# PCB_Telemetria_2020.net
KiCad netlist of a schematic drawn in EAGLE
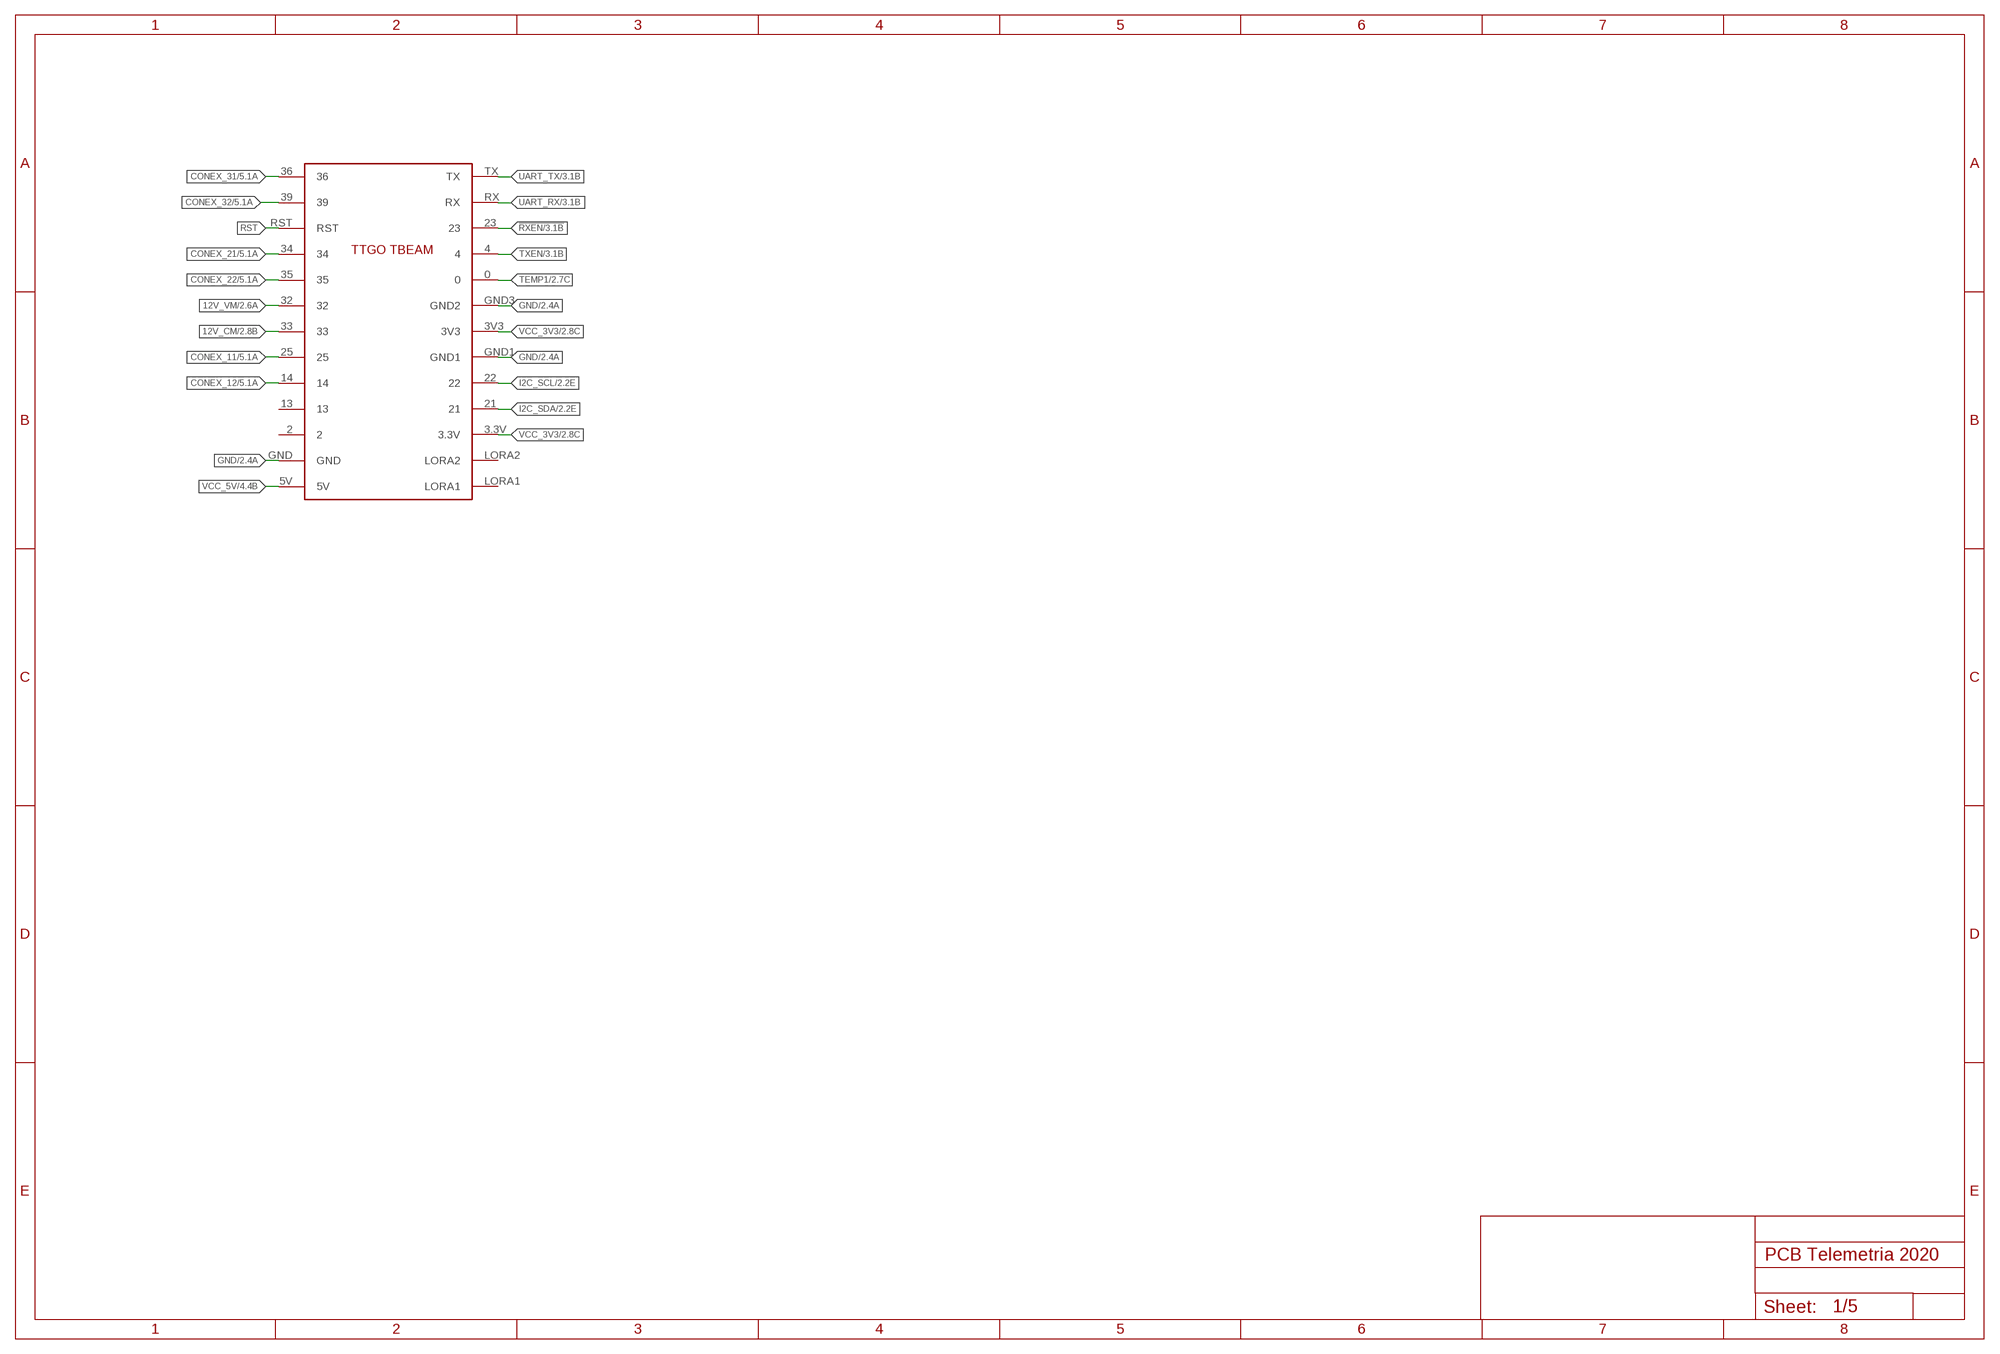
[diagram p0: schematic, sheet 1]
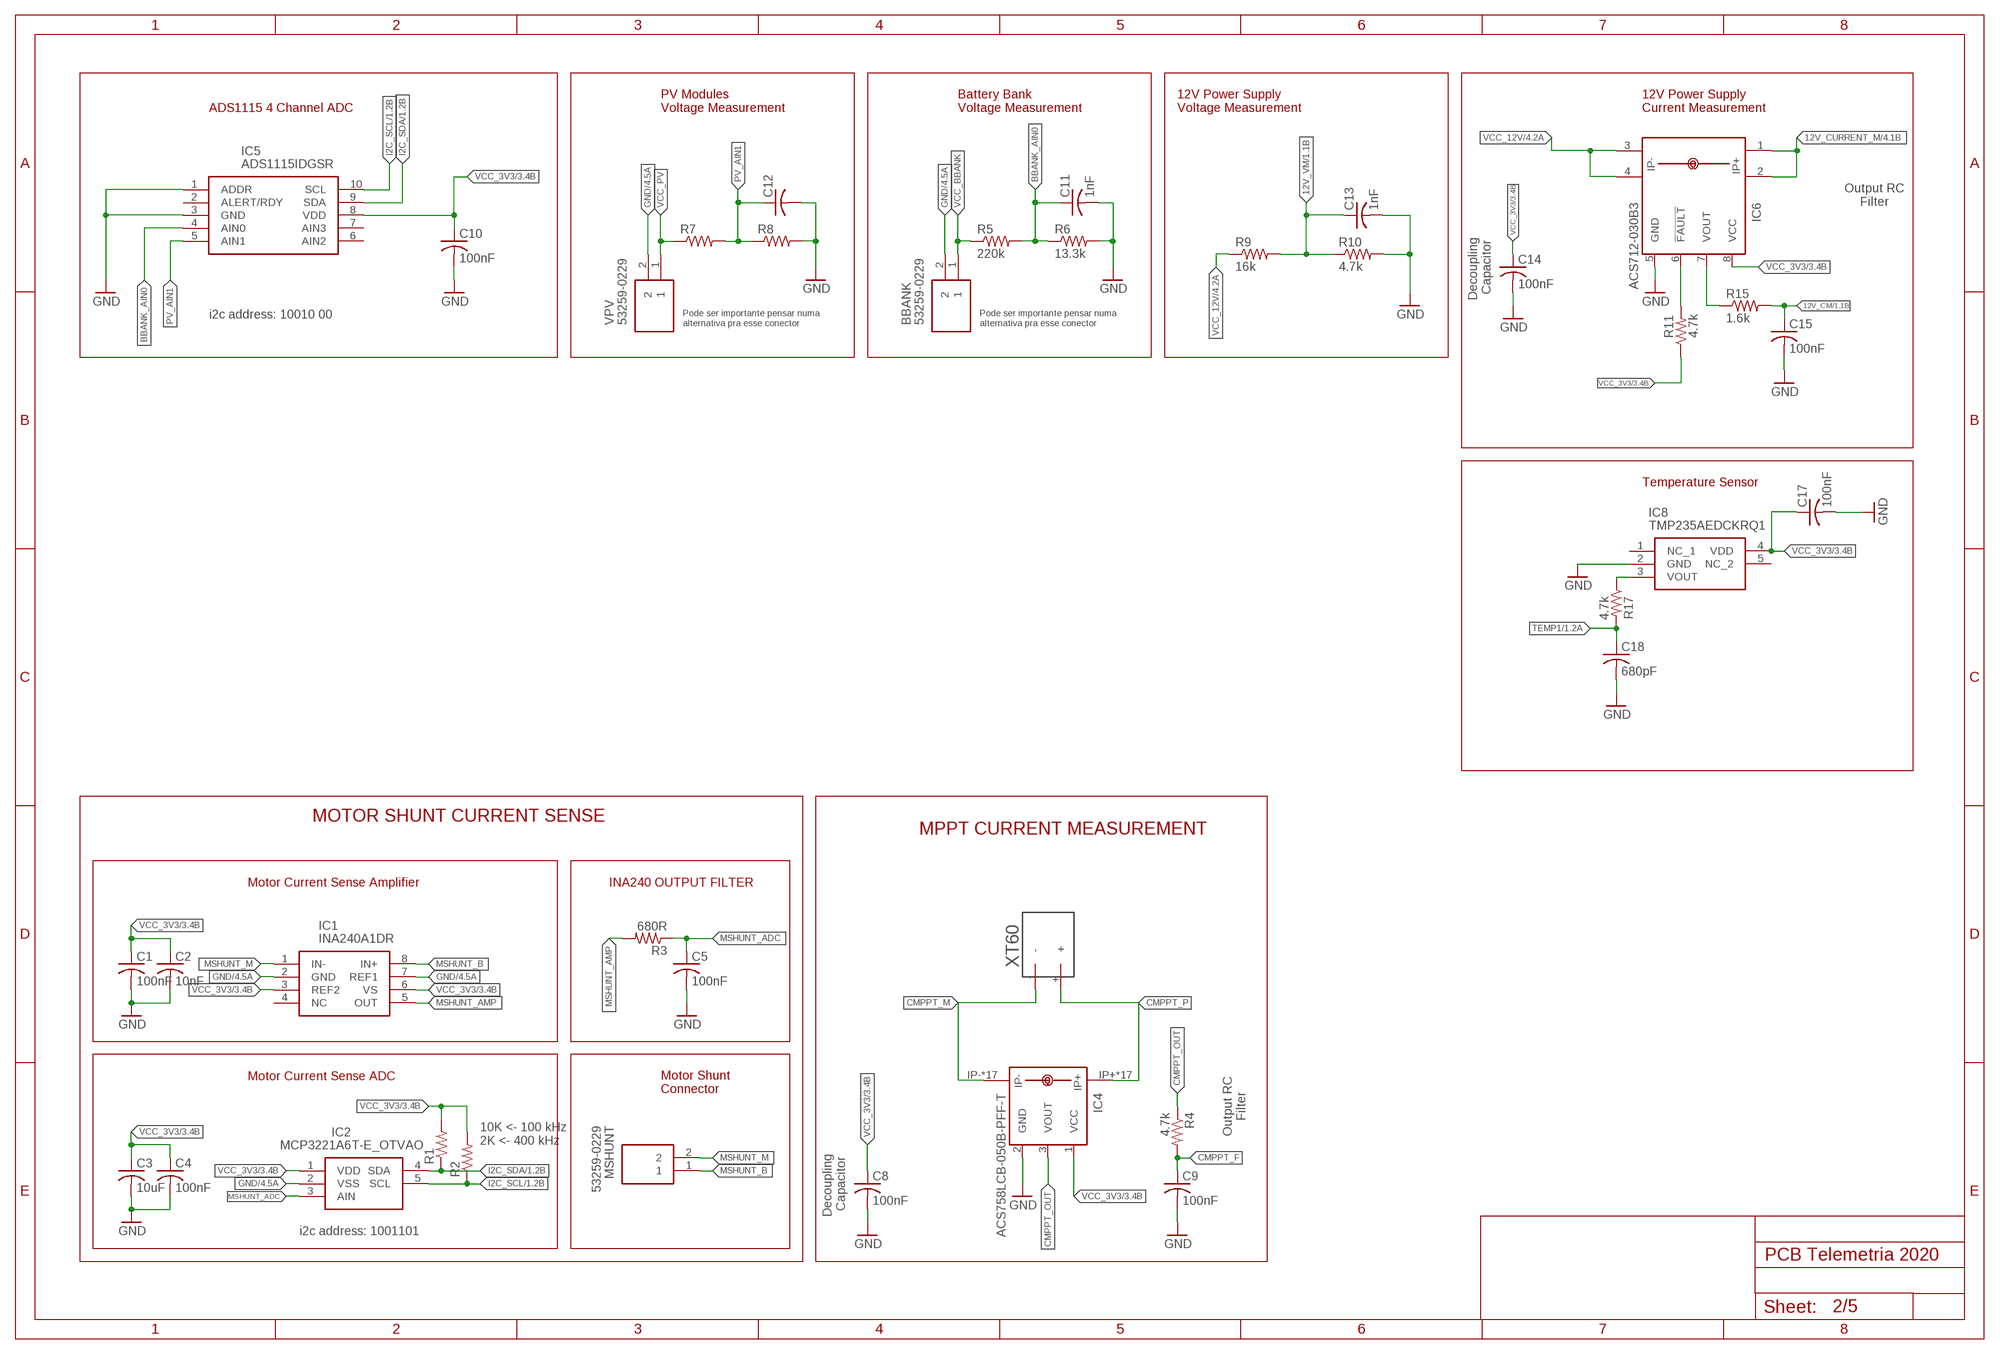
[diagram p1: schematic, sheet 2]
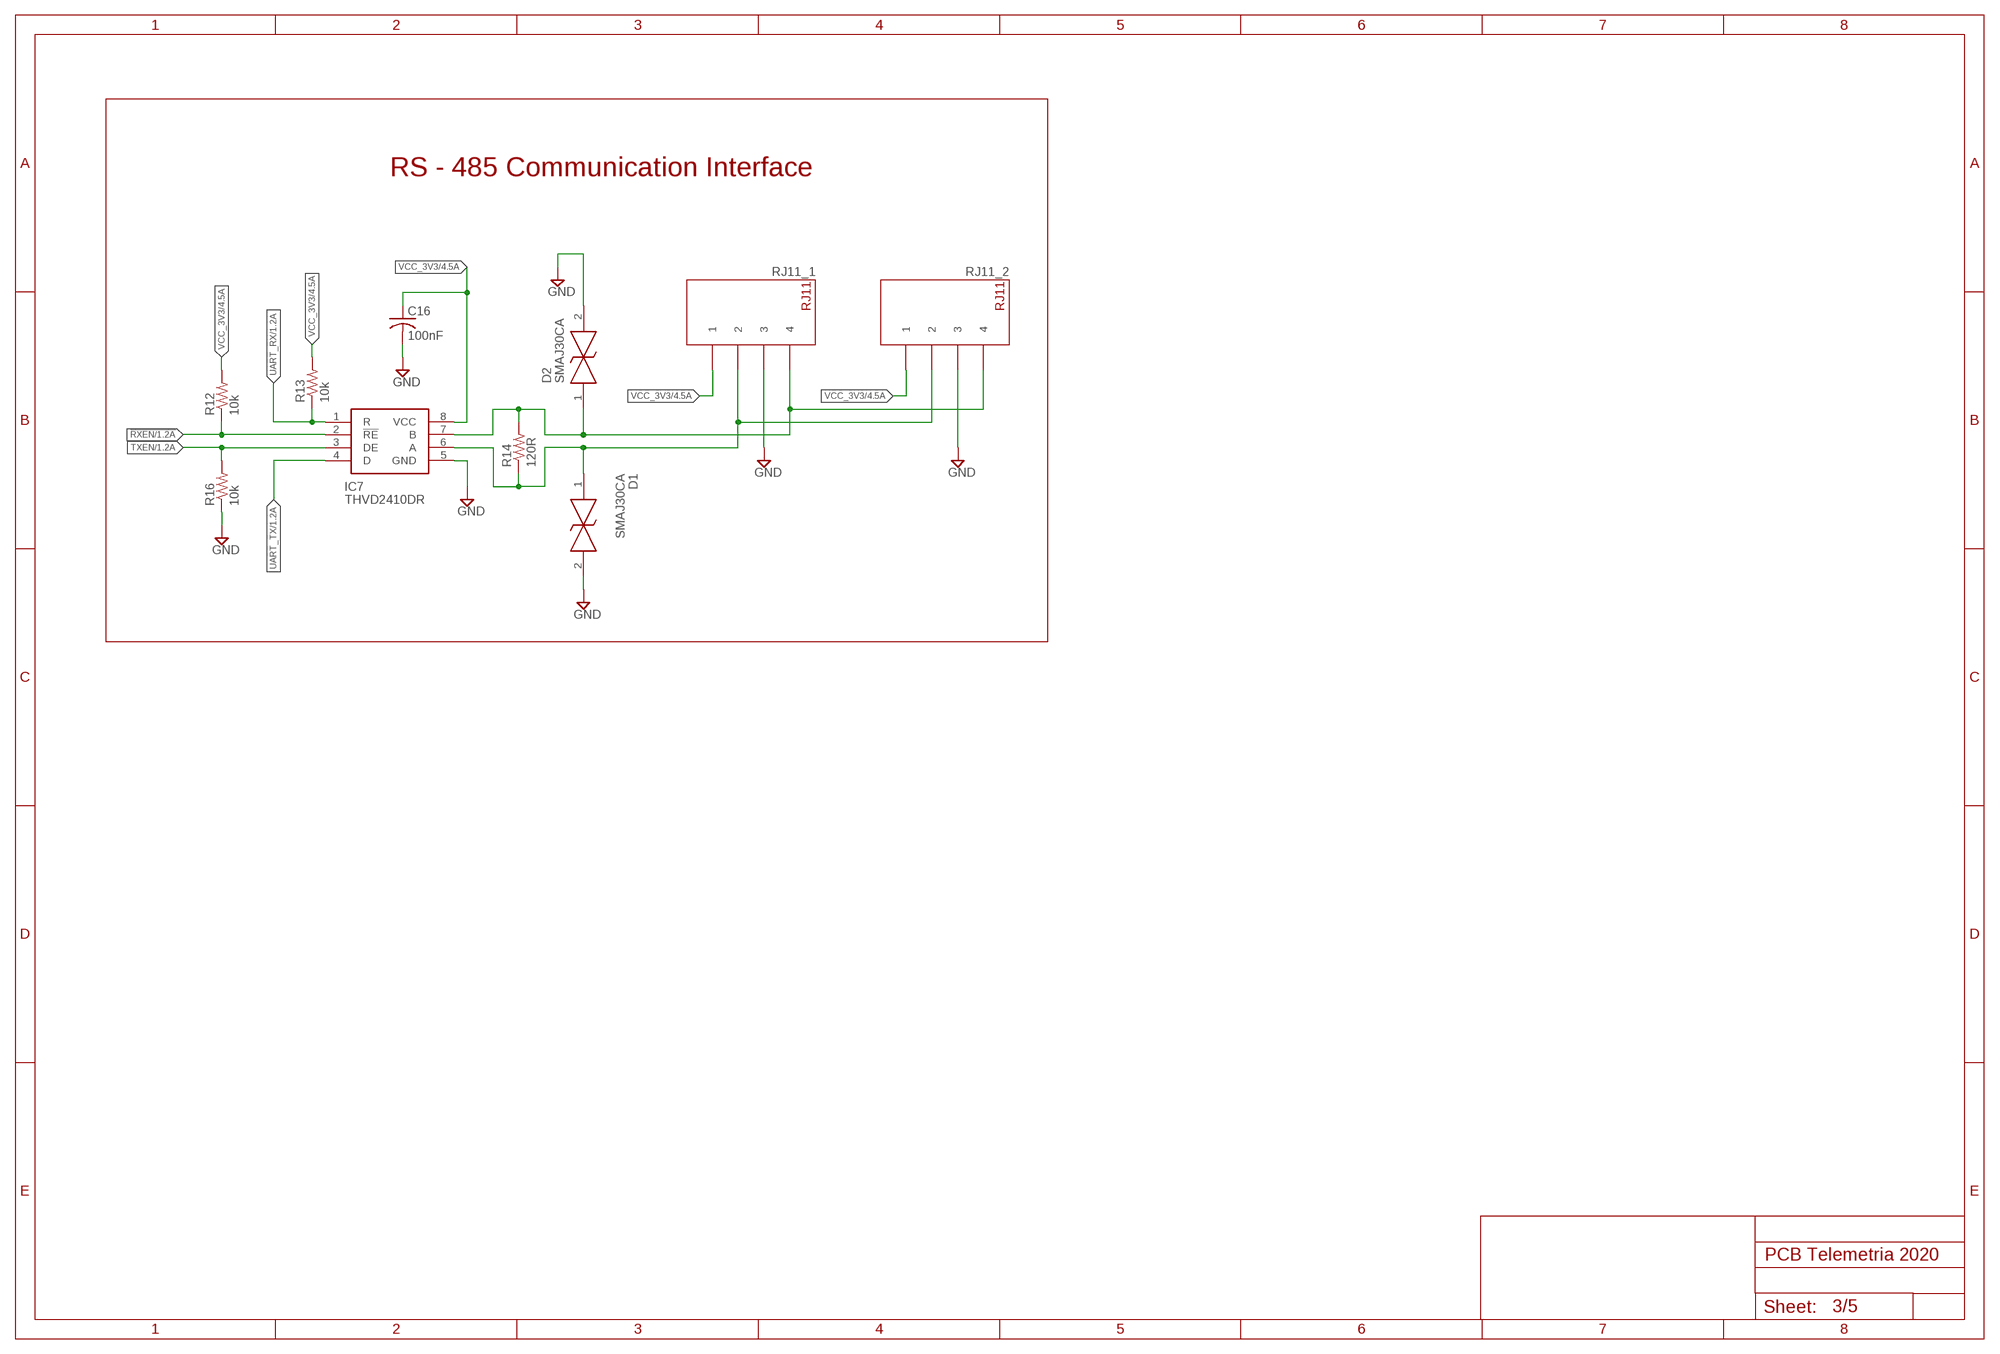
[diagram p2: schematic, sheet 3]
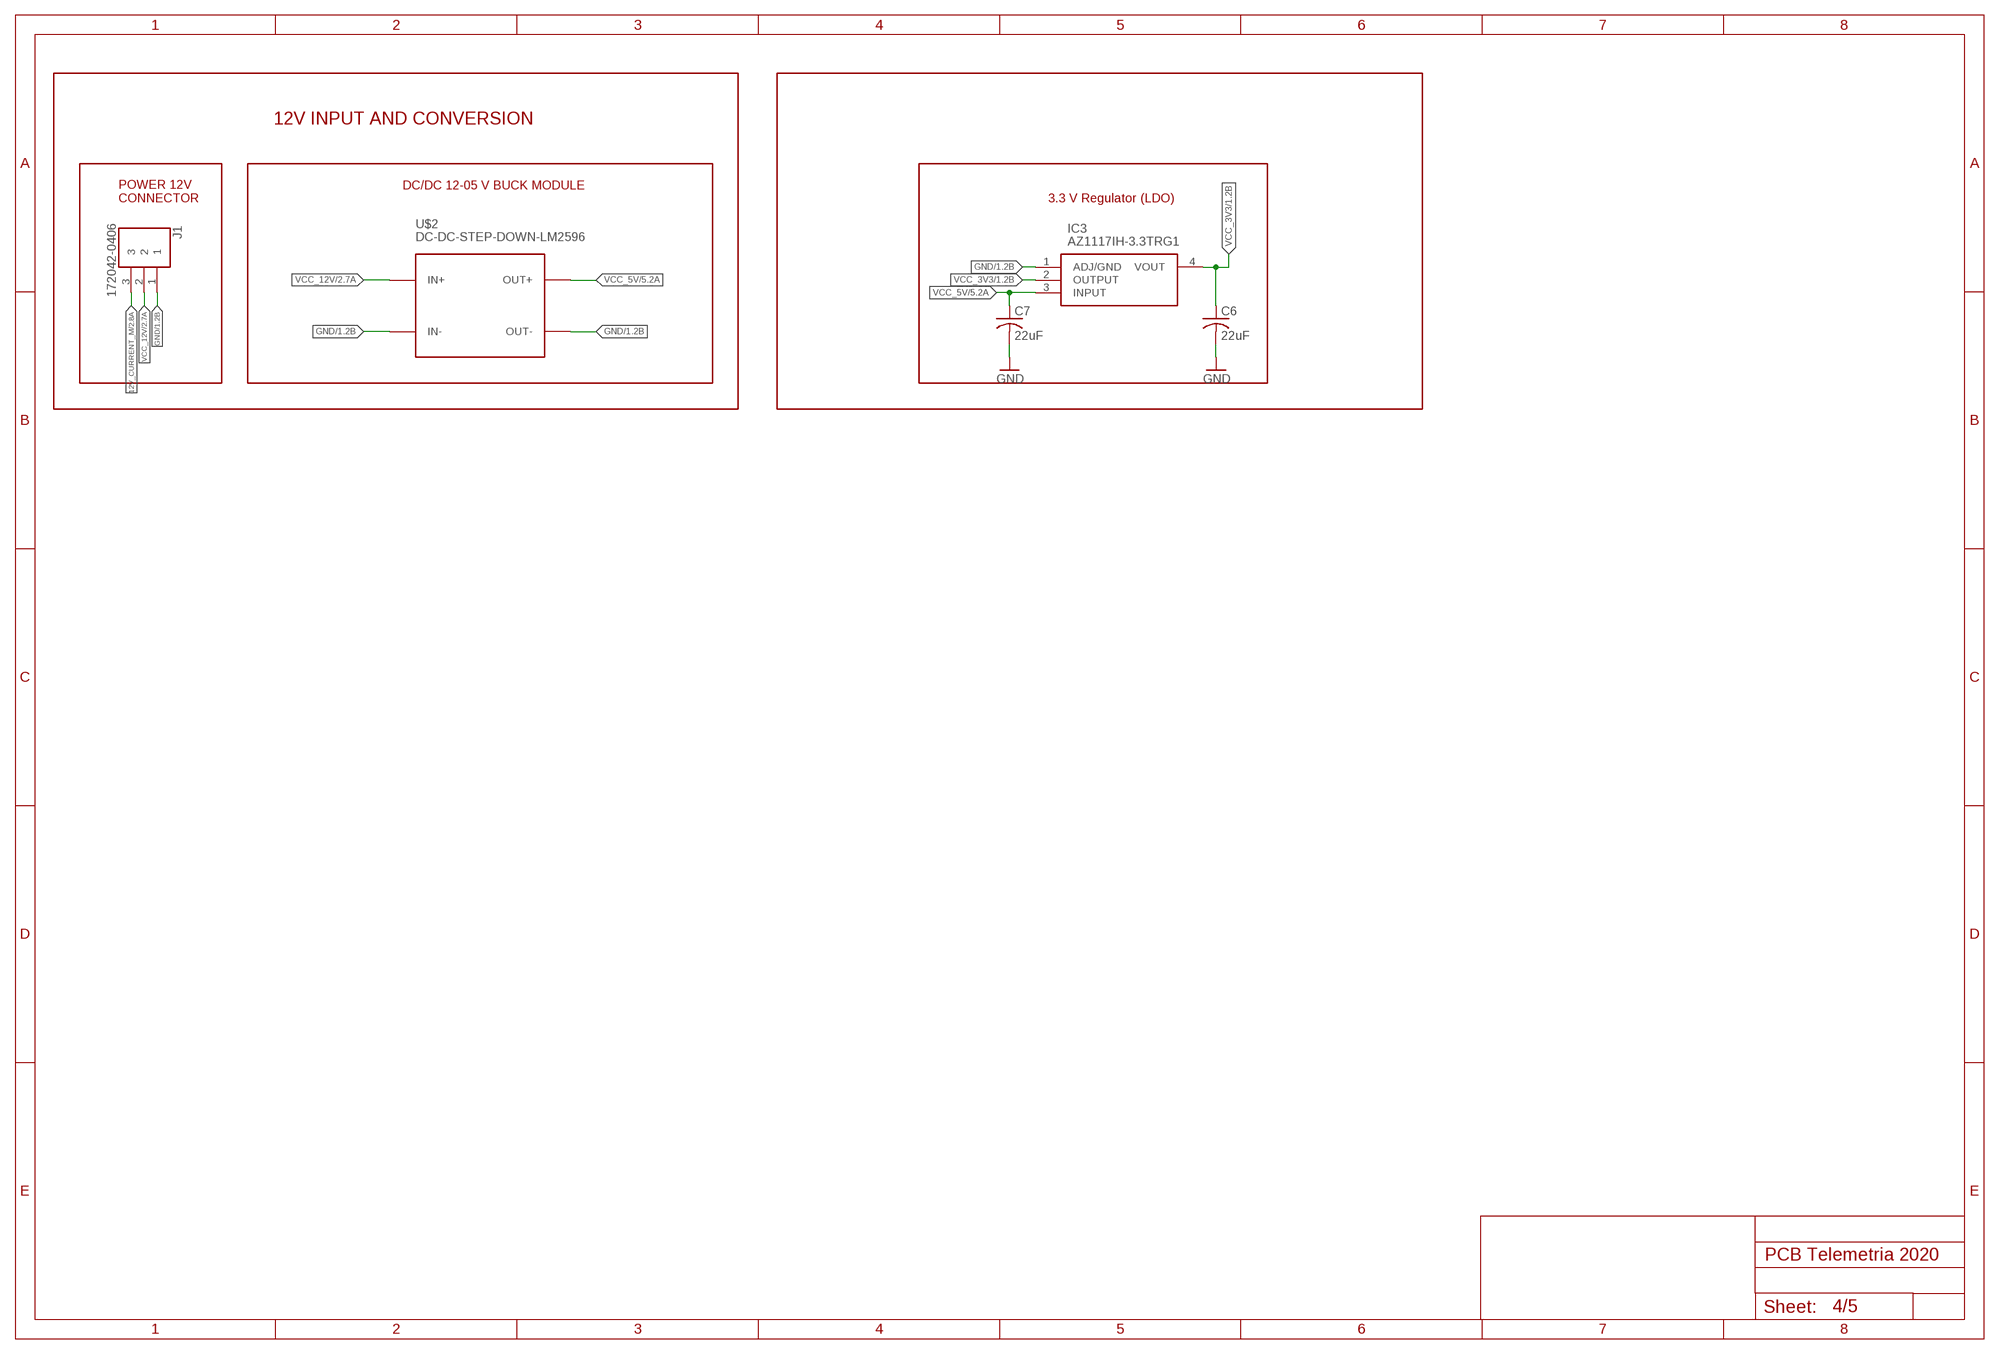
[diagram p3: schematic, sheet 4]
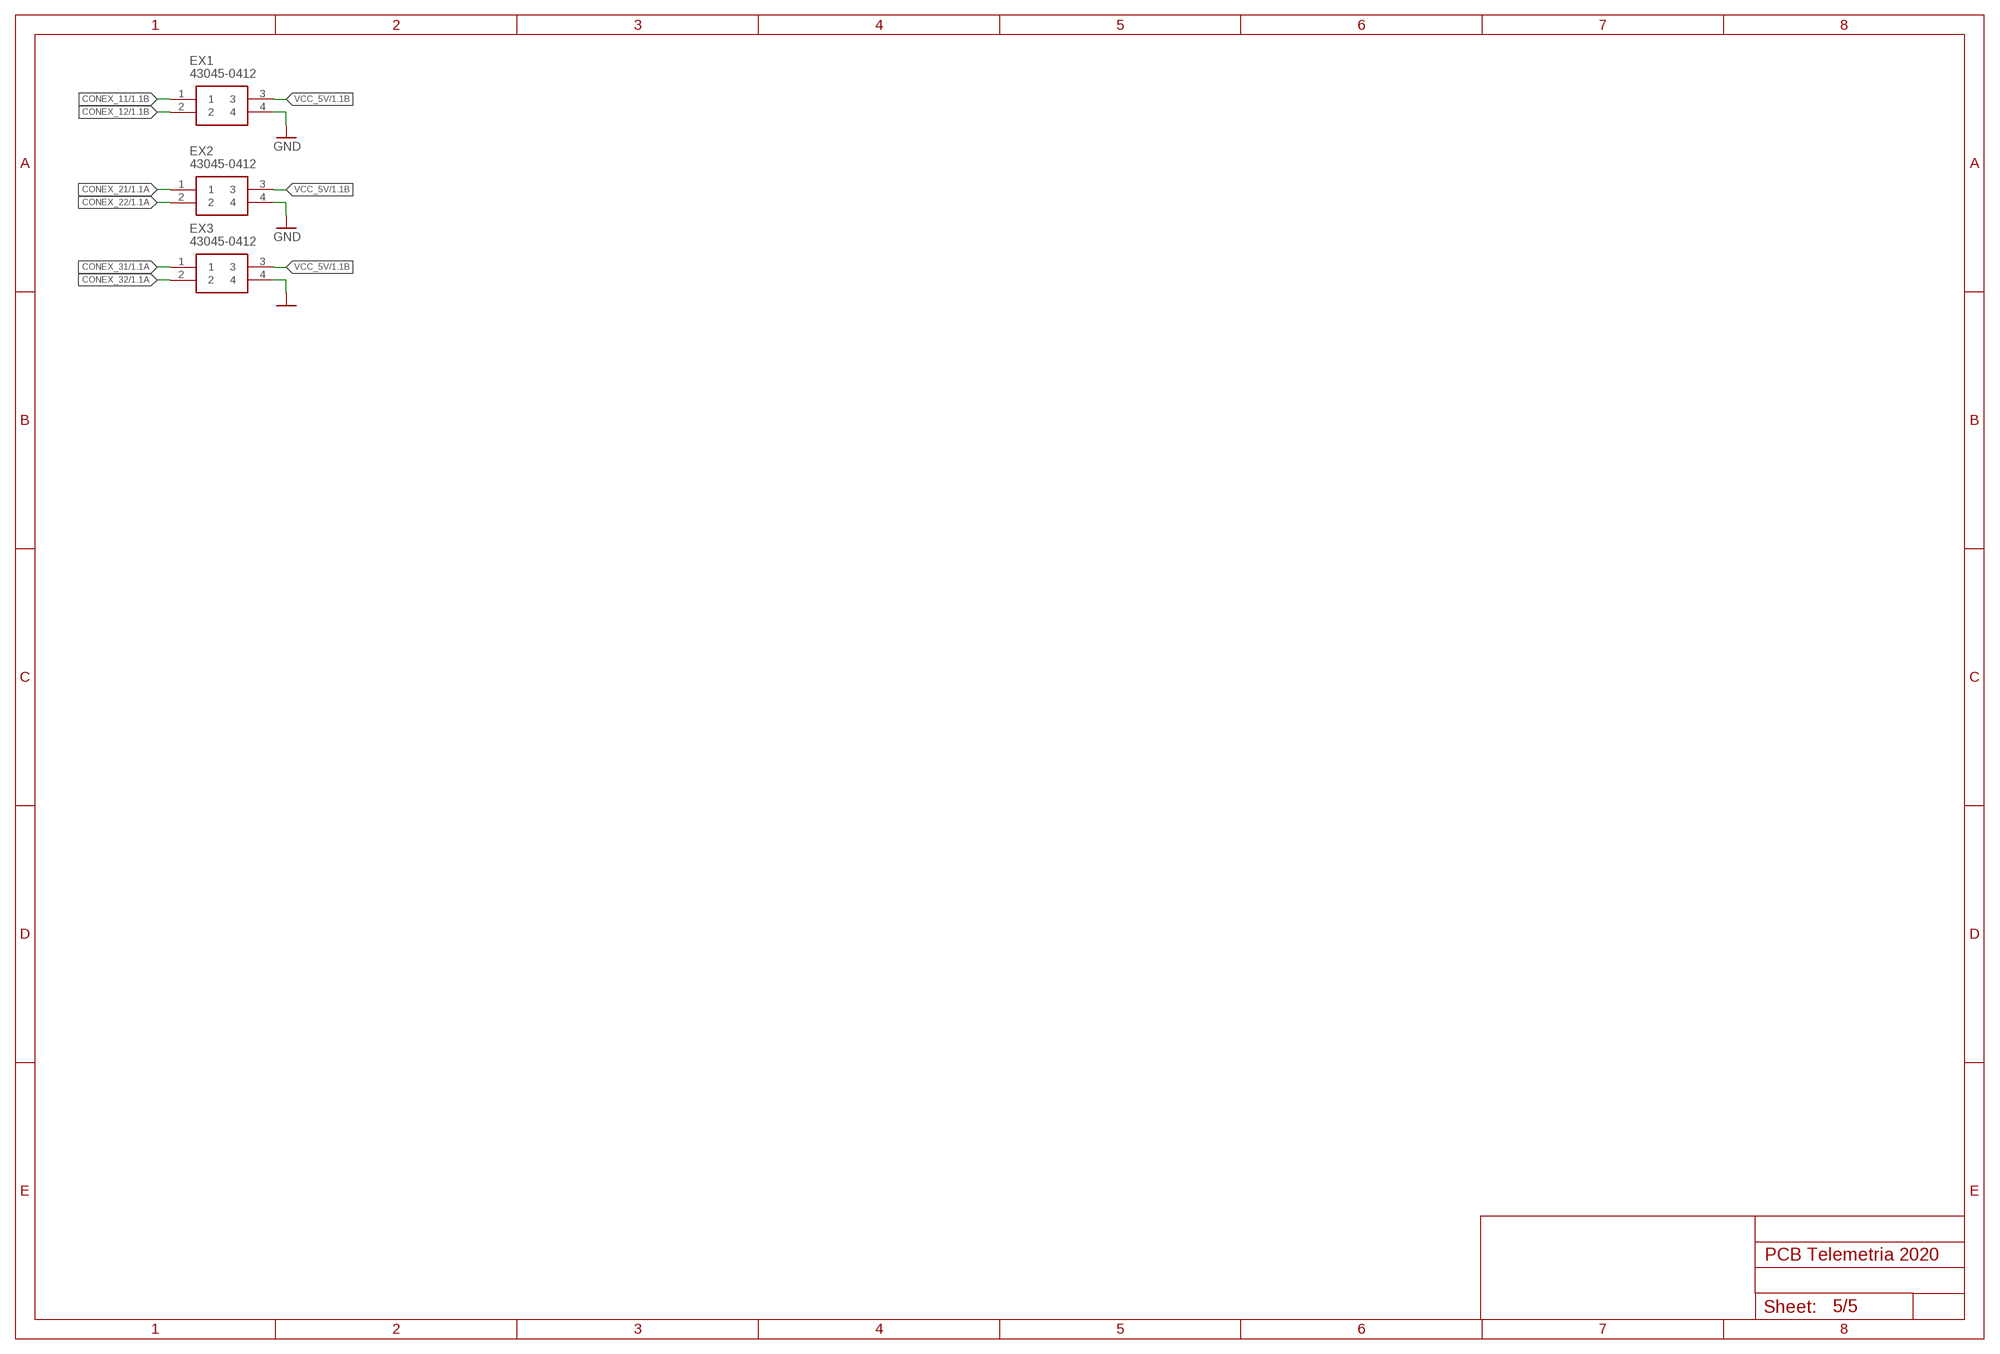
[diagram p4: schematic, sheet 5]

(export (version "E")
  (design (tool "Eeschema 10.0.6"))
  (components
    (comp (ref "C16")
      (value "100nF")
      (footprint "eagle-import:C0805")
      (libsource (lib "eagle-import") (part "C-USC0805"))
    )
    (comp (ref "D1")
      (value "SMAJ30CA")
      (footprint "eagle-import:DIONM5026X229N")
      (fields (field (name "MOUSER_PART_NUMBER") "576-SMAJ30CA"))
      (libsource (lib "eagle-import") (part "SMAJ30CA"))
    )
    (comp (ref "D2")
      (value "SMAJ30CA")
      (footprint "eagle-import:DIONM5026X229N")
      (fields (field (name "MOUSER_PART_NUMBER") "576-SMAJ30CA"))
      (libsource (lib "eagle-import") (part "SMAJ30CA"))
    )
    (comp (ref "IC7")
      (value "THVD2410DR")
      (footprint "eagle-import:SOIC127P600X175-8N")
      (fields (field (name "MOUSER_PART_NUMBER") "595-THVD2410DR"))
      (libsource (lib "eagle-import") (part "THVD2410DR"))
    )
    (comp (ref "R12")
      (value "10k")
      (footprint "eagle-import:M0805")
      (libsource (lib "eagle-import") (part "R-US_M0805"))
    )
    (comp (ref "R13")
      (value "10k")
      (footprint "eagle-import:M0805")
      (libsource (lib "eagle-import") (part "R-US_M0805"))
    )
    (comp (ref "R14")
      (value "120R")
      (footprint "eagle-import:M0805")
      (libsource (lib "eagle-import") (part "R-US_M0805"))
    )
    (comp (ref "R16")
      (value "10k")
      (footprint "eagle-import:M0805")
      (libsource (lib "eagle-import") (part "R-US_M0805"))
    )
    (comp (ref "RJ11_1")
      (value "TFC44")
      (footprint "eagle-import:TFC44")
      (libsource (lib "eagle-import") (part "TFC44"))
    )
    (comp (ref "RJ11_2")
      (value "TFC44")
      (footprint "eagle-import:TFC44")
      (libsource (lib "eagle-import") (part "TFC44"))
    )
    (comp (ref "EX1")
      (value "43045-0412")
      (footprint "eagle-import:43045-0412")
      (fields (field (name "MOUSER_PART_NUMBER") "538-43045-0412"))
      (libsource (lib "eagle-import") (part "43045-0412"))
    )
    (comp (ref "EX2")
      (value "43045-0412")
      (footprint "eagle-import:43045-0412")
      (fields (field (name "MOUSER_PART_NUMBER") "538-43045-0412"))
      (libsource (lib "eagle-import") (part "43045-0412"))
    )
    (comp (ref "EX3")
      (value "43045-0412")
      (footprint "eagle-import:43045-0412")
      (fields (field (name "MOUSER_PART_NUMBER") "538-43045-0412"))
      (libsource (lib "eagle-import") (part "43045-0412"))
    )
    (comp (ref "U$1")
      (value "TTGOBEAM")
      (footprint "eagle-import:TTGOBEAM")
      (libsource (lib "eagle-import") (part "TTGOBEAM"))
    )
    (comp (ref "BBANK")
      (value "53259-0229")
      (footprint "eagle-import:0532590229")
      (fields (field (name "MOUSER_PART_NUMBER") "538-53259-0229"))
      (libsource (lib "eagle-import") (part "53259-0229"))
    )
    (comp (ref "C1")
      (value "100nF")
      (footprint "eagle-import:C0805")
      (libsource (lib "eagle-import") (part "C-USC0805"))
    )
    (comp (ref "C2")
      (value "10nF")
      (footprint "eagle-import:C0805")
      (libsource (lib "eagle-import") (part "C-USC0805"))
    )
    (comp (ref "C3")
      (value "10uF")
      (footprint "eagle-import:C0805")
      (libsource (lib "eagle-import") (part "C-USC0805"))
    )
    (comp (ref "C4")
      (value "100nF")
      (footprint "eagle-import:C0805")
      (libsource (lib "eagle-import") (part "C-USC0805"))
    )
    (comp (ref "C5")
      (value "100nF")
      (footprint "eagle-import:C0805")
      (libsource (lib "eagle-import") (part "C-USC0805"))
    )
    (comp (ref "C8")
      (value "100nF")
      (footprint "eagle-import:C0805")
      (libsource (lib "eagle-import") (part "C-USC0805"))
    )
    (comp (ref "C9")
      (value "100nF")
      (footprint "eagle-import:C0805")
      (libsource (lib "eagle-import") (part "C-USC0805"))
    )
    (comp (ref "C10")
      (value "100nF")
      (footprint "eagle-import:C0805")
      (libsource (lib "eagle-import") (part "C-USC0805"))
    )
    (comp (ref "C11")
      (value "1nF")
      (footprint "eagle-import:C0805")
      (libsource (lib "eagle-import") (part "C-USC0805"))
    )
    (comp (ref "C12")
      (value "C-USC0805")
      (footprint "eagle-import:C0805")
      (libsource (lib "eagle-import") (part "C-USC0805"))
    )
    (comp (ref "C13")
      (value "1nF")
      (footprint "eagle-import:C0805")
      (libsource (lib "eagle-import") (part "C-USC0805"))
    )
    (comp (ref "C14")
      (value "100nF")
      (footprint "eagle-import:C0805")
      (libsource (lib "eagle-import") (part "C-USC0805"))
    )
    (comp (ref "C15")
      (value "100nF")
      (footprint "eagle-import:C0805")
      (libsource (lib "eagle-import") (part "C-USC0805"))
    )
    (comp (ref "C17")
      (value "100nF")
      (footprint "eagle-import:C0805")
      (libsource (lib "eagle-import") (part "C-USC0805"))
    )
    (comp (ref "C18")
      (value "680pF")
      (footprint "eagle-import:C0805")
      (libsource (lib "eagle-import") (part "C-USC0805"))
    )
    (comp (ref "IC1")
      (value "INA240A1DR")
      (footprint "eagle-import:SOIC127P600X175-8N")
      (fields (field (name "MOUSER_PART_NUMBER") "595-INA240A1DR"))
      (libsource (lib "eagle-import") (part "INA240A1DR"))
    )
    (comp (ref "IC2")
      (value "MCP3221A6T-E_OTVAO")
      (footprint "eagle-import:SOT95P280X145-5N")
      (fields
        (field (name "MANUFACTURER_PART_NUMBER") "MCP3221A6T-E/OTVAO")
        (field (name "MOUSER_PART_NUMBER") "579-MCP3221A6TEOTVAO")
      )
      (libsource (lib "eagle-import") (part "MCP3221A6T-E_OTVAO"))
    )
    (comp (ref "IC4")
      (value "ACS758LCB-050B-PFF-T")
      (footprint "eagle-import:CB-PFF")
      (libsource (lib "eagle-import") (part "ACS758LCB-050B-PFF-T"))
    )
    (comp (ref "IC5")
      (value "ADS1115IDGSR")
      (footprint "eagle-import:SOP50P490X110-10N")
      (fields (field (name "MOUSER_PART_NUMBER") "595-ADS1115IDGSR"))
      (libsource (lib "eagle-import") (part "ADS1115IDGSR"))
    )
    (comp (ref "IC6")
      (value "ACS712-030B3")
      (footprint "eagle-import:SOIC8")
      (libsource (lib "eagle-import") (part "ACS712-LC"))
    )
    (comp (ref "IC8")
      (value "TMP235AEDCKRQ1")
      (footprint "eagle-import:SOT65P210X110-5N")
      (fields (field (name "MOUSER_PART_NUMBER") "595-TMP235AEDCKRQ1"))
      (libsource (lib "eagle-import") (part "TMP235AEDCKRQ1"))
    )
    (comp (ref "MSHUNT")
      (value "53259-0229")
      (footprint "eagle-import:0532590229")
      (fields (field (name "MOUSER_PART_NUMBER") "538-53259-0229"))
      (libsource (lib "eagle-import") (part "53259-0229"))
    )
    (comp (ref "R1")
      (value "R-US_R0805")
      (footprint "eagle-import:R0805")
      (libsource (lib "eagle-import") (part "R-US_R0805"))
    )
    (comp (ref "R2")
      (value "R-US_R0805")
      (footprint "eagle-import:R0805")
      (libsource (lib "eagle-import") (part "R-US_R0805"))
    )
    (comp (ref "R3")
      (value "680R")
      (footprint "eagle-import:R0805")
      (libsource (lib "eagle-import") (part "R-US_R0805"))
    )
    (comp (ref "R4")
      (value "4.7k")
      (footprint "eagle-import:R0805")
      (libsource (lib "eagle-import") (part "R-US_R0805"))
    )
    (comp (ref "R5")
      (value "220k")
      (footprint "eagle-import:R0805")
      (libsource (lib "eagle-import") (part "R-US_R0805"))
    )
    (comp (ref "R6")
      (value "13.3k")
      (footprint "eagle-import:R0805")
      (libsource (lib "eagle-import") (part "R-US_R0805"))
    )
    (comp (ref "R7")
      (value "R-US_R0805")
      (footprint "eagle-import:R0805")
      (libsource (lib "eagle-import") (part "R-US_R0805"))
    )
    (comp (ref "R8")
      (value "R-US_R0805")
      (footprint "eagle-import:R0805")
      (libsource (lib "eagle-import") (part "R-US_R0805"))
    )
    (comp (ref "R9")
      (value "16k")
      (footprint "eagle-import:R0805")
      (libsource (lib "eagle-import") (part "R-US_R0805"))
    )
    (comp (ref "R10")
      (value "4.7k")
      (footprint "eagle-import:R0805")
      (libsource (lib "eagle-import") (part "R-US_R0805"))
    )
    (comp (ref "R11")
      (value "4.7k")
      (footprint "eagle-import:R0805")
      (libsource (lib "eagle-import") (part "R-US_R0805"))
    )
    (comp (ref "R15")
      (value "1.6k")
      (footprint "eagle-import:R0805")
      (libsource (lib "eagle-import") (part "R-US_R0805"))
    )
    (comp (ref "R17")
      (value "4.7k")
      (footprint "eagle-import:R0805")
      (libsource (lib "eagle-import") (part "R-US_R0805"))
    )
    (comp (ref "U$3")
      (value "XT60")
      (footprint "eagle-import:XT60")
      (libsource (lib "eagle-import") (part "XT60"))
    )
    (comp (ref "VPV")
      (value "53259-0229")
      (footprint "eagle-import:0532590229")
      (fields (field (name "MOUSER_PART_NUMBER") "538-53259-0229"))
      (libsource (lib "eagle-import") (part "53259-0229"))
    )
    (comp (ref "C6")
      (value "22uF")
      (footprint "eagle-import:C0805")
      (libsource (lib "eagle-import") (part "C-USC0805"))
    )
    (comp (ref "C7")
      (value "22uF")
      (footprint "eagle-import:C0805")
      (libsource (lib "eagle-import") (part "C-USC0805"))
    )
    (comp (ref "IC3")
      (value "AZ1117IH-3.3TRG1")
      (footprint "eagle-import:SOT230P700X170-4N")
      (fields (field (name "MOUSER_PART_NUMBER") "621-AZ1117IH-3.3TRG1"))
      (libsource (lib "eagle-import") (part "AZ1117IH-3.3TRG1"))
    )
    (comp (ref "J1")
      (value "172042-0406")
      (footprint "eagle-import:MOLEX_172042-0406")
      (fields (field (name "MF") "Molex") (field (name "MP") "172042-0302"))
      (libsource (lib "eagle-import") (part "172042-0406"))
    )
    (comp (ref "U$2")
      (value "DC-DC-STEP-DOWN-LM2596")
      (footprint "eagle-import:DC-DC-STEP-DOWN-LM2596")
      (libsource (lib "eagle-import") (part "DC-DC-STEP-DOWN-LM2596"))
    )
  )
  (nets
    (net (code "1") (name "12V_CM") (class "Default")
      (node (ref "C15") (pin "1") (pinfunction "1_1") (pintype "passive"))
      (node (ref "R15") (pin "2") (pinfunction "2_2") (pintype "passive"))
      (node (ref "U$1") (pin "33") (pinfunction "33_33") (pintype "bidirectional"))
    )
    (net (code "2") (name "12V_CURRENT_M") (class "Default")
      (node (ref "IC6") (pin "1") (pinfunction "IP+_1") (pintype "passive"))
      (node (ref "IC6") (pin "2") (pinfunction "IP+1_2") (pintype "passive"))
      (node (ref "J1") (pin "3") (pinfunction "3_3") (pintype "passive"))
    )
    (net (code "3") (name "12V_VM") (class "Default")
      (node (ref "C13") (pin "1") (pinfunction "1_1") (pintype "passive"))
      (node (ref "R10") (pin "1") (pinfunction "1_1") (pintype "passive"))
      (node (ref "R9") (pin "2") (pinfunction "2_2") (pintype "passive"))
      (node (ref "U$1") (pin "32") (pinfunction "32_32") (pintype "bidirectional"))
    )
    (net (code "4") (name "BBANK_AIN0") (class "Default")
      (node (ref "C11") (pin "1") (pinfunction "1_1") (pintype "passive"))
      (node (ref "IC5") (pin "4") (pinfunction "AIN0_4") (pintype "bidirectional"))
      (node (ref "R5") (pin "2") (pinfunction "2_2") (pintype "passive"))
      (node (ref "R6") (pin "1") (pinfunction "1_1") (pintype "passive"))
    )
    (net (code "5") (name "CMPPT_F") (class "Default")
      (node (ref "C9") (pin "1") (pinfunction "1_1") (pintype "passive"))
      (node (ref "R4") (pin "2") (pinfunction "2_2") (pintype "passive"))
    )
    (net (code "6") (name "CMPPT_M") (class "Default")
      (node (ref "IC4") (pin "IP-") (pinfunction "IP-_IP-") (pintype "passive"))
      (node (ref "IC4") (pin "IP-@10") (pinfunction "IP-_IP-@10") (pintype "passive"))
      (node (ref "IC4") (pin "IP-@11") (pinfunction "IP-_IP-@11") (pintype "passive"))
      (node (ref "IC4") (pin "IP-@12") (pinfunction "IP-_IP-@12") (pintype "passive"))
      (node (ref "IC4") (pin "IP-@13") (pinfunction "IP-_IP-@13") (pintype "passive"))
      (node (ref "IC4") (pin "IP-@14") (pinfunction "IP-_IP-@14") (pintype "passive"))
      (node (ref "IC4") (pin "IP-@15") (pinfunction "IP-_IP-@15") (pintype "passive"))
      (node (ref "IC4") (pin "IP-@16") (pinfunction "IP-_IP-@16") (pintype "passive"))
      (node (ref "IC4") (pin "IP-@17") (pinfunction "IP-_IP-@17") (pintype "passive"))
      (node (ref "IC4") (pin "IP-@2") (pinfunction "IP-_IP-@2") (pintype "passive"))
      (node (ref "IC4") (pin "IP-@3") (pinfunction "IP-_IP-@3") (pintype "passive"))
      (node (ref "IC4") (pin "IP-@4") (pinfunction "IP-_IP-@4") (pintype "passive"))
      (node (ref "IC4") (pin "IP-@5") (pinfunction "IP-_IP-@5") (pintype "passive"))
      (node (ref "IC4") (pin "IP-@6") (pinfunction "IP-_IP-@6") (pintype "passive"))
      (node (ref "IC4") (pin "IP-@7") (pinfunction "IP-_IP-@7") (pintype "passive"))
      (node (ref "IC4") (pin "IP-@8") (pinfunction "IP-_IP-@8") (pintype "passive"))
      (node (ref "IC4") (pin "IP-@9") (pinfunction "IP-_IP-@9") (pintype "passive"))
      (node (ref "U$3") (pin "-") (pinfunction "-_-") (pintype "bidirectional"))
    )
    (net (code "7") (name "CMPPT_OUT") (class "Default")
      (node (ref "IC4") (pin "3") (pinfunction "VOUT_3") (pintype "output"))
      (node (ref "R4") (pin "1") (pinfunction "1_1") (pintype "passive"))
    )
    (net (code "8") (name "CMPPT_P") (class "Default")
      (node (ref "IC4") (pin "IP+") (pinfunction "IP+_IP+") (pintype "passive"))
      (node (ref "IC4") (pin "IP+@10") (pinfunction "IP+_IP+@10") (pintype "passive"))
      (node (ref "IC4") (pin "IP+@11") (pinfunction "IP+_IP+@11") (pintype "passive"))
      (node (ref "IC4") (pin "IP+@12") (pinfunction "IP+_IP+@12") (pintype "passive"))
      (node (ref "IC4") (pin "IP+@13") (pinfunction "IP+_IP+@13") (pintype "passive"))
      (node (ref "IC4") (pin "IP+@14") (pinfunction "IP+_IP+@14") (pintype "passive"))
      (node (ref "IC4") (pin "IP+@15") (pinfunction "IP+_IP+@15") (pintype "passive"))
      (node (ref "IC4") (pin "IP+@16") (pinfunction "IP+_IP+@16") (pintype "passive"))
      (node (ref "IC4") (pin "IP+@17") (pinfunction "IP+_IP+@17") (pintype "passive"))
      (node (ref "IC4") (pin "IP+@2") (pinfunction "IP+_IP+@2") (pintype "passive"))
      (node (ref "IC4") (pin "IP+@3") (pinfunction "IP+_IP+@3") (pintype "passive"))
      (node (ref "IC4") (pin "IP+@4") (pinfunction "IP+_IP+@4") (pintype "passive"))
      (node (ref "IC4") (pin "IP+@5") (pinfunction "IP+_IP+@5") (pintype "passive"))
      (node (ref "IC4") (pin "IP+@6") (pinfunction "IP+_IP+@6") (pintype "passive"))
      (node (ref "IC4") (pin "IP+@7") (pinfunction "IP+_IP+@7") (pintype "passive"))
      (node (ref "IC4") (pin "IP+@8") (pinfunction "IP+_IP+@8") (pintype "passive"))
      (node (ref "IC4") (pin "IP+@9") (pinfunction "IP+_IP+@9") (pintype "passive"))
      (node (ref "U$3") (pin "+") (pinfunction "+_+") (pintype "bidirectional"))
    )
    (net (code "9") (name "CONEX_11") (class "Default")
      (node (ref "EX1") (pin "1") (pinfunction "1_1") (pintype "bidirectional"))
      (node (ref "U$1") (pin "25") (pinfunction "25_25") (pintype "bidirectional"))
    )
    (net (code "10") (name "CONEX_12") (class "Default")
      (node (ref "EX1") (pin "2") (pinfunction "2_2") (pintype "bidirectional"))
      (node (ref "U$1") (pin "14") (pinfunction "14_14") (pintype "bidirectional"))
    )
    (net (code "11") (name "CONEX_21") (class "Default")
      (node (ref "EX2") (pin "1") (pinfunction "1_1") (pintype "bidirectional"))
      (node (ref "U$1") (pin "34") (pinfunction "34_34") (pintype "bidirectional"))
    )
    (net (code "12") (name "CONEX_22") (class "Default")
      (node (ref "EX2") (pin "2") (pinfunction "2_2") (pintype "bidirectional"))
      (node (ref "U$1") (pin "35") (pinfunction "35_35") (pintype "bidirectional"))
    )
    (net (code "13") (name "CONEX_31") (class "Default")
      (node (ref "EX3") (pin "1") (pinfunction "1_1") (pintype "bidirectional"))
      (node (ref "U$1") (pin "36") (pinfunction "36_36") (pintype "bidirectional"))
    )
    (net (code "14") (name "CONEX_32") (class "Default")
      (node (ref "EX3") (pin "2") (pinfunction "2_2") (pintype "bidirectional"))
      (node (ref "U$1") (pin "39") (pinfunction "39_39") (pintype "bidirectional"))
    )
    (net (code "15") (name "GND") (class "Default")
      (node (ref "BBANK") (pin "2") (pinfunction "2_2") (pintype "bidirectional"))
      (node (ref "C1") (pin "2") (pinfunction "2_2") (pintype "passive"))
      (node (ref "C10") (pin "2") (pinfunction "2_2") (pintype "passive"))
      (node (ref "C11") (pin "2") (pinfunction "2_2") (pintype "passive"))
      (node (ref "C12") (pin "2") (pinfunction "2_2") (pintype "passive"))
      (node (ref "C13") (pin "2") (pinfunction "2_2") (pintype "passive"))
      (node (ref "C14") (pin "2") (pinfunction "2_2") (pintype "passive"))
      (node (ref "C15") (pin "2") (pinfunction "2_2") (pintype "passive"))
      (node (ref "C16") (pin "2") (pinfunction "2_2") (pintype "passive"))
      (node (ref "C17") (pin "2") (pinfunction "2_2") (pintype "passive"))
      (node (ref "C18") (pin "2") (pinfunction "2_2") (pintype "passive"))
      (node (ref "C2") (pin "2") (pinfunction "2_2") (pintype "passive"))
      (node (ref "C3") (pin "2") (pinfunction "2_2") (pintype "passive"))
      (node (ref "C4") (pin "2") (pinfunction "2_2") (pintype "passive"))
      (node (ref "C5") (pin "2") (pinfunction "2_2") (pintype "passive"))
      (node (ref "C6") (pin "2") (pinfunction "2_2") (pintype "passive"))
      (node (ref "C7") (pin "2") (pinfunction "2_2") (pintype "passive"))
      (node (ref "C8") (pin "2") (pinfunction "2_2") (pintype "passive"))
      (node (ref "C9") (pin "2") (pinfunction "2_2") (pintype "passive"))
      (node (ref "D1") (pin "2") (pinfunction "2_2") (pintype "bidirectional"))
      (node (ref "D2") (pin "2") (pinfunction "2_2") (pintype "bidirectional"))
      (node (ref "EX1") (pin "4") (pinfunction "4_4") (pintype "bidirectional"))
      (node (ref "EX2") (pin "4") (pinfunction "4_4") (pintype "bidirectional"))
      (node (ref "EX3") (pin "4") (pinfunction "4_4") (pintype "bidirectional"))
      (node (ref "IC1") (pin "2") (pinfunction "GND_2") (pintype "bidirectional"))
      (node (ref "IC1") (pin "7") (pinfunction "REF1_7") (pintype "bidirectional"))
      (node (ref "IC2") (pin "2") (pinfunction "VSS_2") (pintype "bidirectional"))
      (node (ref "IC3") (pin "1") (pinfunction "ADJ/GND_1") (pintype "bidirectional"))
      (node (ref "IC4") (pin "2") (pinfunction "GND_2") (pintype "power_in"))
      (node (ref "IC5") (pin "1") (pinfunction "ADDR_1") (pintype "bidirectional"))
      (node (ref "IC5") (pin "3") (pinfunction "GND_3") (pintype "bidirectional"))
      (node (ref "IC6") (pin "5") (pinfunction "GND_5") (pintype "power_in"))
      (node (ref "IC7") (pin "5") (pinfunction "GND_5") (pintype "bidirectional"))
      (node (ref "IC8") (pin "2") (pinfunction "GND_2") (pintype "bidirectional"))
      (node (ref "J1") (pin "1") (pinfunction "1_1") (pintype "passive"))
      (node (ref "R10") (pin "2") (pinfunction "2_2") (pintype "passive"))
      (node (ref "R16") (pin "1") (pinfunction "1_1") (pintype "passive"))
      (node (ref "R6") (pin "2") (pinfunction "2_2") (pintype "passive"))
      (node (ref "R8") (pin "2") (pinfunction "2_2") (pintype "passive"))
      (node (ref "RJ11_1") (pin "P$3") (pinfunction "3_P$3") (pintype "bidirectional"))
      (node (ref "RJ11_2") (pin "P$3") (pinfunction "3_P$3") (pintype "bidirectional"))
      (node (ref "U$1") (pin "GND") (pinfunction "GND_GND") (pintype "bidirectional"))
      (node (ref "U$1") (pin "GND1") (pinfunction "GND1_GND1") (pintype "bidirectional"))
      (node (ref "U$1") (pin "GND3") (pinfunction "GND2_GND3") (pintype "bidirectional"))
      (node (ref "U$2") (pin "IN-") (pinfunction "IN-_IN-") (pintype "bidirectional"))
      (node (ref "U$2") (pin "OUT-") (pinfunction "OUT-_OUT-") (pintype "bidirectional"))
      (node (ref "VPV") (pin "2") (pinfunction "2_2") (pintype "bidirectional"))
    )
    (net (code "16") (name "I2C_SCL") (class "Default")
      (node (ref "IC2") (pin "5") (pinfunction "SCL_5") (pintype "bidirectional"))
      (node (ref "IC5") (pin "10") (pinfunction "SCL_10") (pintype "bidirectional"))
      (node (ref "R2") (pin "1") (pinfunction "1_1") (pintype "passive"))
      (node (ref "U$1") (pin "22") (pinfunction "22_22") (pintype "bidirectional"))
    )
    (net (code "17") (name "I2C_SDA") (class "Default")
      (node (ref "IC2") (pin "4") (pinfunction "SDA_4") (pintype "bidirectional"))
      (node (ref "IC5") (pin "9") (pinfunction "SDA_9") (pintype "bidirectional"))
      (node (ref "R1") (pin "1") (pinfunction "1_1") (pintype "passive"))
      (node (ref "U$1") (pin "21") (pinfunction "21_21") (pintype "bidirectional"))
    )
    (net (code "18") (name "MSHUNT_ADC") (class "Default")
      (node (ref "C5") (pin "1") (pinfunction "1_1") (pintype "passive"))
      (node (ref "IC2") (pin "3") (pinfunction "AIN_3") (pintype "bidirectional"))
      (node (ref "R3") (pin "1") (pinfunction "1_1") (pintype "passive"))
    )
    (net (code "19") (name "MSHUNT_AMP") (class "Default")
      (node (ref "IC1") (pin "5") (pinfunction "OUT_5") (pintype "bidirectional"))
      (node (ref "R3") (pin "2") (pinfunction "2_2") (pintype "passive"))
    )
    (net (code "20") (name "MSHUNT_B") (class "Default")
      (node (ref "IC1") (pin "8") (pinfunction "IN+_8") (pintype "bidirectional"))
      (node (ref "MSHUNT") (pin "1") (pinfunction "1_1") (pintype "bidirectional"))
    )
    (net (code "21") (name "MSHUNT_M") (class "Default")
      (node (ref "IC1") (pin "1") (pinfunction "IN-_1") (pintype "bidirectional"))
      (node (ref "MSHUNT") (pin "2") (pinfunction "2_2") (pintype "bidirectional"))
    )
    (net (code "22") (name "Net-(IC6-VOUT)") (class "Default")
      (node (ref "IC6") (pin "7") (pinfunction "VOUT_7") (pintype "output"))
      (node (ref "R15") (pin "1") (pinfunction "1_1") (pintype "passive"))
    )
    (net (code "23") (name "Net-(IC6-~{FAULT})") (class "Default")
      (node (ref "IC6") (pin "6") (pinfunction "~{FAULT}_6") (pintype "bidirectional"))
      (node (ref "R11") (pin "2") (pinfunction "2_2") (pintype "passive"))
    )
    (net (code "24") (name "Net-(IC7-A)") (class "Default")
      (node (ref "D1") (pin "1") (pinfunction "1_1") (pintype "bidirectional"))
      (node (ref "IC7") (pin "6") (pinfunction "A_6") (pintype "bidirectional"))
      (node (ref "R14") (pin "1") (pinfunction "1_1") (pintype "passive"))
      (node (ref "RJ11_1") (pin "P$2") (pinfunction "2_P$2") (pintype "bidirectional"))
      (node (ref "RJ11_2") (pin "P$2") (pinfunction "2_P$2") (pintype "bidirectional"))
    )
    (net (code "25") (name "Net-(IC7-B)") (class "Default")
      (node (ref "D2") (pin "1") (pinfunction "1_1") (pintype "bidirectional"))
      (node (ref "IC7") (pin "7") (pinfunction "B_7") (pintype "bidirectional"))
      (node (ref "R14") (pin "2") (pinfunction "2_2") (pintype "passive"))
      (node (ref "RJ11_1") (pin "P$4") (pinfunction "4_P$4") (pintype "bidirectional"))
      (node (ref "RJ11_2") (pin "P$4") (pinfunction "4_P$4") (pintype "bidirectional"))
    )
    (net (code "26") (name "Net-(IC8-VOUT)") (class "Default")
      (node (ref "IC8") (pin "3") (pinfunction "VOUT_3") (pintype "bidirectional"))
      (node (ref "R17") (pin "1") (pinfunction "1_1") (pintype "passive"))
    )
    (net (code "27") (name "PV_AIN1") (class "Default")
      (node (ref "C12") (pin "1") (pinfunction "1_1") (pintype "passive"))
      (node (ref "IC5") (pin "5") (pinfunction "AIN1_5") (pintype "bidirectional"))
      (node (ref "R7") (pin "2") (pinfunction "2_2") (pintype "passive"))
      (node (ref "R8") (pin "1") (pinfunction "1_1") (pintype "passive"))
    )
    (net (code "28") (name "RST") (class "Default")
      (node (ref "U$1") (pin "RST") (pinfunction "RST_RST") (pintype "bidirectional"))
    )
    (net (code "29") (name "TEMP1") (class "Default")
      (node (ref "C18") (pin "1") (pinfunction "1_1") (pintype "passive"))
      (node (ref "R17") (pin "2") (pinfunction "2_2") (pintype "passive"))
      (node (ref "U$1") (pin "0") (pinfunction "0_0") (pintype "bidirectional"))
    )
    (net (code "30") (name "TXEN") (class "Default")
      (node (ref "IC7") (pin "3") (pinfunction "DE_3") (pintype "bidirectional"))
      (node (ref "R16") (pin "2") (pinfunction "2_2") (pintype "passive"))
      (node (ref "U$1") (pin "4") (pinfunction "4_4") (pintype "bidirectional"))
    )
    (net (code "31") (name "UART_RX") (class "Default")
      (node (ref "IC7") (pin "1") (pinfunction "R_1") (pintype "bidirectional"))
      (node (ref "R13") (pin "1") (pinfunction "1_1") (pintype "passive"))
      (node (ref "U$1") (pin "RX") (pinfunction "RX_RX") (pintype "bidirectional"))
    )
    (net (code "32") (name "UART_TX") (class "Default")
      (node (ref "IC7") (pin "4") (pinfunction "D_4") (pintype "bidirectional"))
      (node (ref "U$1") (pin "TX") (pinfunction "TX_TX") (pintype "bidirectional"))
    )
    (net (code "33") (name "VCC_3V3") (class "Default")
      (node (ref "C1") (pin "1") (pinfunction "1_1") (pintype "passive"))
      (node (ref "C10") (pin "1") (pinfunction "1_1") (pintype "passive"))
      (node (ref "C14") (pin "1") (pinfunction "1_1") (pintype "passive"))
      (node (ref "C16") (pin "1") (pinfunction "1_1") (pintype "passive"))
      (node (ref "C17") (pin "1") (pinfunction "1_1") (pintype "passive"))
      (node (ref "C2") (pin "1") (pinfunction "1_1") (pintype "passive"))
      (node (ref "C3") (pin "1") (pinfunction "1_1") (pintype "passive"))
      (node (ref "C4") (pin "1") (pinfunction "1_1") (pintype "passive"))
      (node (ref "C6") (pin "1") (pinfunction "1_1") (pintype "passive"))
      (node (ref "C8") (pin "1") (pinfunction "1_1") (pintype "passive"))
      (node (ref "IC1") (pin "3") (pinfunction "REF2_3") (pintype "bidirectional"))
      (node (ref "IC1") (pin "6") (pinfunction "VS_6") (pintype "bidirectional"))
      (node (ref "IC2") (pin "1") (pinfunction "VDD_1") (pintype "bidirectional"))
      (node (ref "IC3") (pin "2") (pinfunction "OUTPUT_2") (pintype "bidirectional"))
      (node (ref "IC3") (pin "4") (pinfunction "VOUT_4") (pintype "bidirectional"))
      (node (ref "IC4") (pin "1") (pinfunction "VCC_1") (pintype "power_in"))
      (node (ref "IC5") (pin "8") (pinfunction "VDD_8") (pintype "bidirectional"))
      (node (ref "IC6") (pin "8") (pinfunction "VCC_8") (pintype "power_in"))
      (node (ref "IC7") (pin "8") (pinfunction "VCC_8") (pintype "bidirectional"))
      (node (ref "IC8") (pin "4") (pinfunction "VDD_4") (pintype "bidirectional"))
      (node (ref "R1") (pin "2") (pinfunction "2_2") (pintype "passive"))
      (node (ref "R11") (pin "1") (pinfunction "1_1") (pintype "passive"))
      (node (ref "R12") (pin "2") (pinfunction "2_2") (pintype "passive"))
      (node (ref "R13") (pin "2") (pinfunction "2_2") (pintype "passive"))
      (node (ref "R2") (pin "2") (pinfunction "2_2") (pintype "passive"))
      (node (ref "RJ11_1") (pin "P$1") (pinfunction "1_P$1") (pintype "bidirectional"))
      (node (ref "RJ11_2") (pin "P$1") (pinfunction "1_P$1") (pintype "bidirectional"))
      (node (ref "U$1") (pin "3.3V") (pinfunction "3.3V_3.3V") (pintype "bidirectional"))
      (node (ref "U$1") (pin "3V3") (pinfunction "3V3_3V3") (pintype "bidirectional"))
    )
    (net (code "34") (name "VCC_5V") (class "Default")
      (node (ref "C7") (pin "1") (pinfunction "1_1") (pintype "passive"))
      (node (ref "EX1") (pin "3") (pinfunction "3_3") (pintype "bidirectional"))
      (node (ref "EX2") (pin "3") (pinfunction "3_3") (pintype "bidirectional"))
      (node (ref "EX3") (pin "3") (pinfunction "3_3") (pintype "bidirectional"))
      (node (ref "IC3") (pin "3") (pinfunction "INPUT_3") (pintype "bidirectional"))
      (node (ref "U$1") (pin "5V") (pinfunction "5V_5V") (pintype "bidirectional"))
      (node (ref "U$2") (pin "OUT+") (pinfunction "OUT+_OUT+") (pintype "bidirectional"))
    )
    (net (code "35") (name "VCC_12V") (class "Default")
      (node (ref "IC6") (pin "3") (pinfunction "IP-_3") (pintype "passive"))
      (node (ref "IC6") (pin "4") (pinfunction "IP-1_4") (pintype "passive"))
      (node (ref "J1") (pin "2") (pinfunction "2_2") (pintype "passive"))
      (node (ref "R9") (pin "1") (pinfunction "1_1") (pintype "passive"))
      (node (ref "U$2") (pin "IN+") (pinfunction "IN+_IN+") (pintype "bidirectional"))
    )
    (net (code "36") (name "VCC_BBANK") (class "Default")
      (node (ref "BBANK") (pin "1") (pinfunction "1_1") (pintype "bidirectional"))
      (node (ref "R5") (pin "1") (pinfunction "1_1") (pintype "passive"))
    )
    (net (code "37") (name "VCC_PV") (class "Default")
      (node (ref "R7") (pin "1") (pinfunction "1_1") (pintype "passive"))
      (node (ref "VPV") (pin "1") (pinfunction "1_1") (pintype "bidirectional"))
    )
    (net (code "38") (name "unconnected-(IC1-NC-Pad4)") (class "Default")
      (node (ref "IC1") (pin "4") (pinfunction "NC_4") (pintype "no_connect"))
    )
    (net (code "39") (name "unconnected-(IC5-AIN2-Pad6)") (class "Default")
      (node (ref "IC5") (pin "6") (pinfunction "AIN2_6") (pintype "bidirectional"))
    )
    (net (code "40") (name "unconnected-(IC5-AIN3-Pad7)") (class "Default")
      (node (ref "IC5") (pin "7") (pinfunction "AIN3_7") (pintype "bidirectional"))
    )
    (net (code "41") (name "unconnected-(IC5-ALERT{slash}RDY-Pad2)") (class "Default")
      (node (ref "IC5") (pin "2") (pinfunction "ALERT/RDY_2") (pintype "bidirectional"))
    )
    (net (code "42") (name "unconnected-(IC8-NC_1-Pad1)") (class "Default")
      (node (ref "IC8") (pin "1") (pinfunction "NC_1_1") (pintype "bidirectional"))
    )
    (net (code "43") (name "unconnected-(IC8-NC_2-Pad5)") (class "Default")
      (node (ref "IC8") (pin "5") (pinfunction "NC_2_5") (pintype "bidirectional"))
    )
    (net (code "44") (name "unconnected-(U$1-Pad2)") (class "Default")
      (node (ref "U$1") (pin "2") (pinfunction "2_2") (pintype "bidirectional"))
    )
    (net (code "45") (name "unconnected-(U$1-Pad13)") (class "Default")
      (node (ref "U$1") (pin "13") (pinfunction "13_13") (pintype "bidirectional"))
    )
    (net (code "46") (name "unconnected-(U$1-PadLORA1)") (class "Default")
      (node (ref "U$1") (pin "LORA1") (pinfunction "LORA1_LORA1") (pintype "bidirectional"))
    )
    (net (code "47") (name "unconnected-(U$1-PadLORA2)") (class "Default")
      (node (ref "U$1") (pin "LORA2") (pinfunction "LORA2_LORA2") (pintype "bidirectional"))
    )
    (net (code "48") (name "~{RXEN}") (class "Default")
      (node (ref "IC7") (pin "2") (pinfunction "~{RE}_2") (pintype "bidirectional"))
      (node (ref "R12") (pin "1") (pinfunction "1_1") (pintype "passive"))
      (node (ref "U$1") (pin "23") (pinfunction "23_23") (pintype "bidirectional"))
    )
  )
)
